# SCH_efoil_tracker_v1_0_2026-07-30.net
KiCad netlist of a schematic drawn in EasyEDA
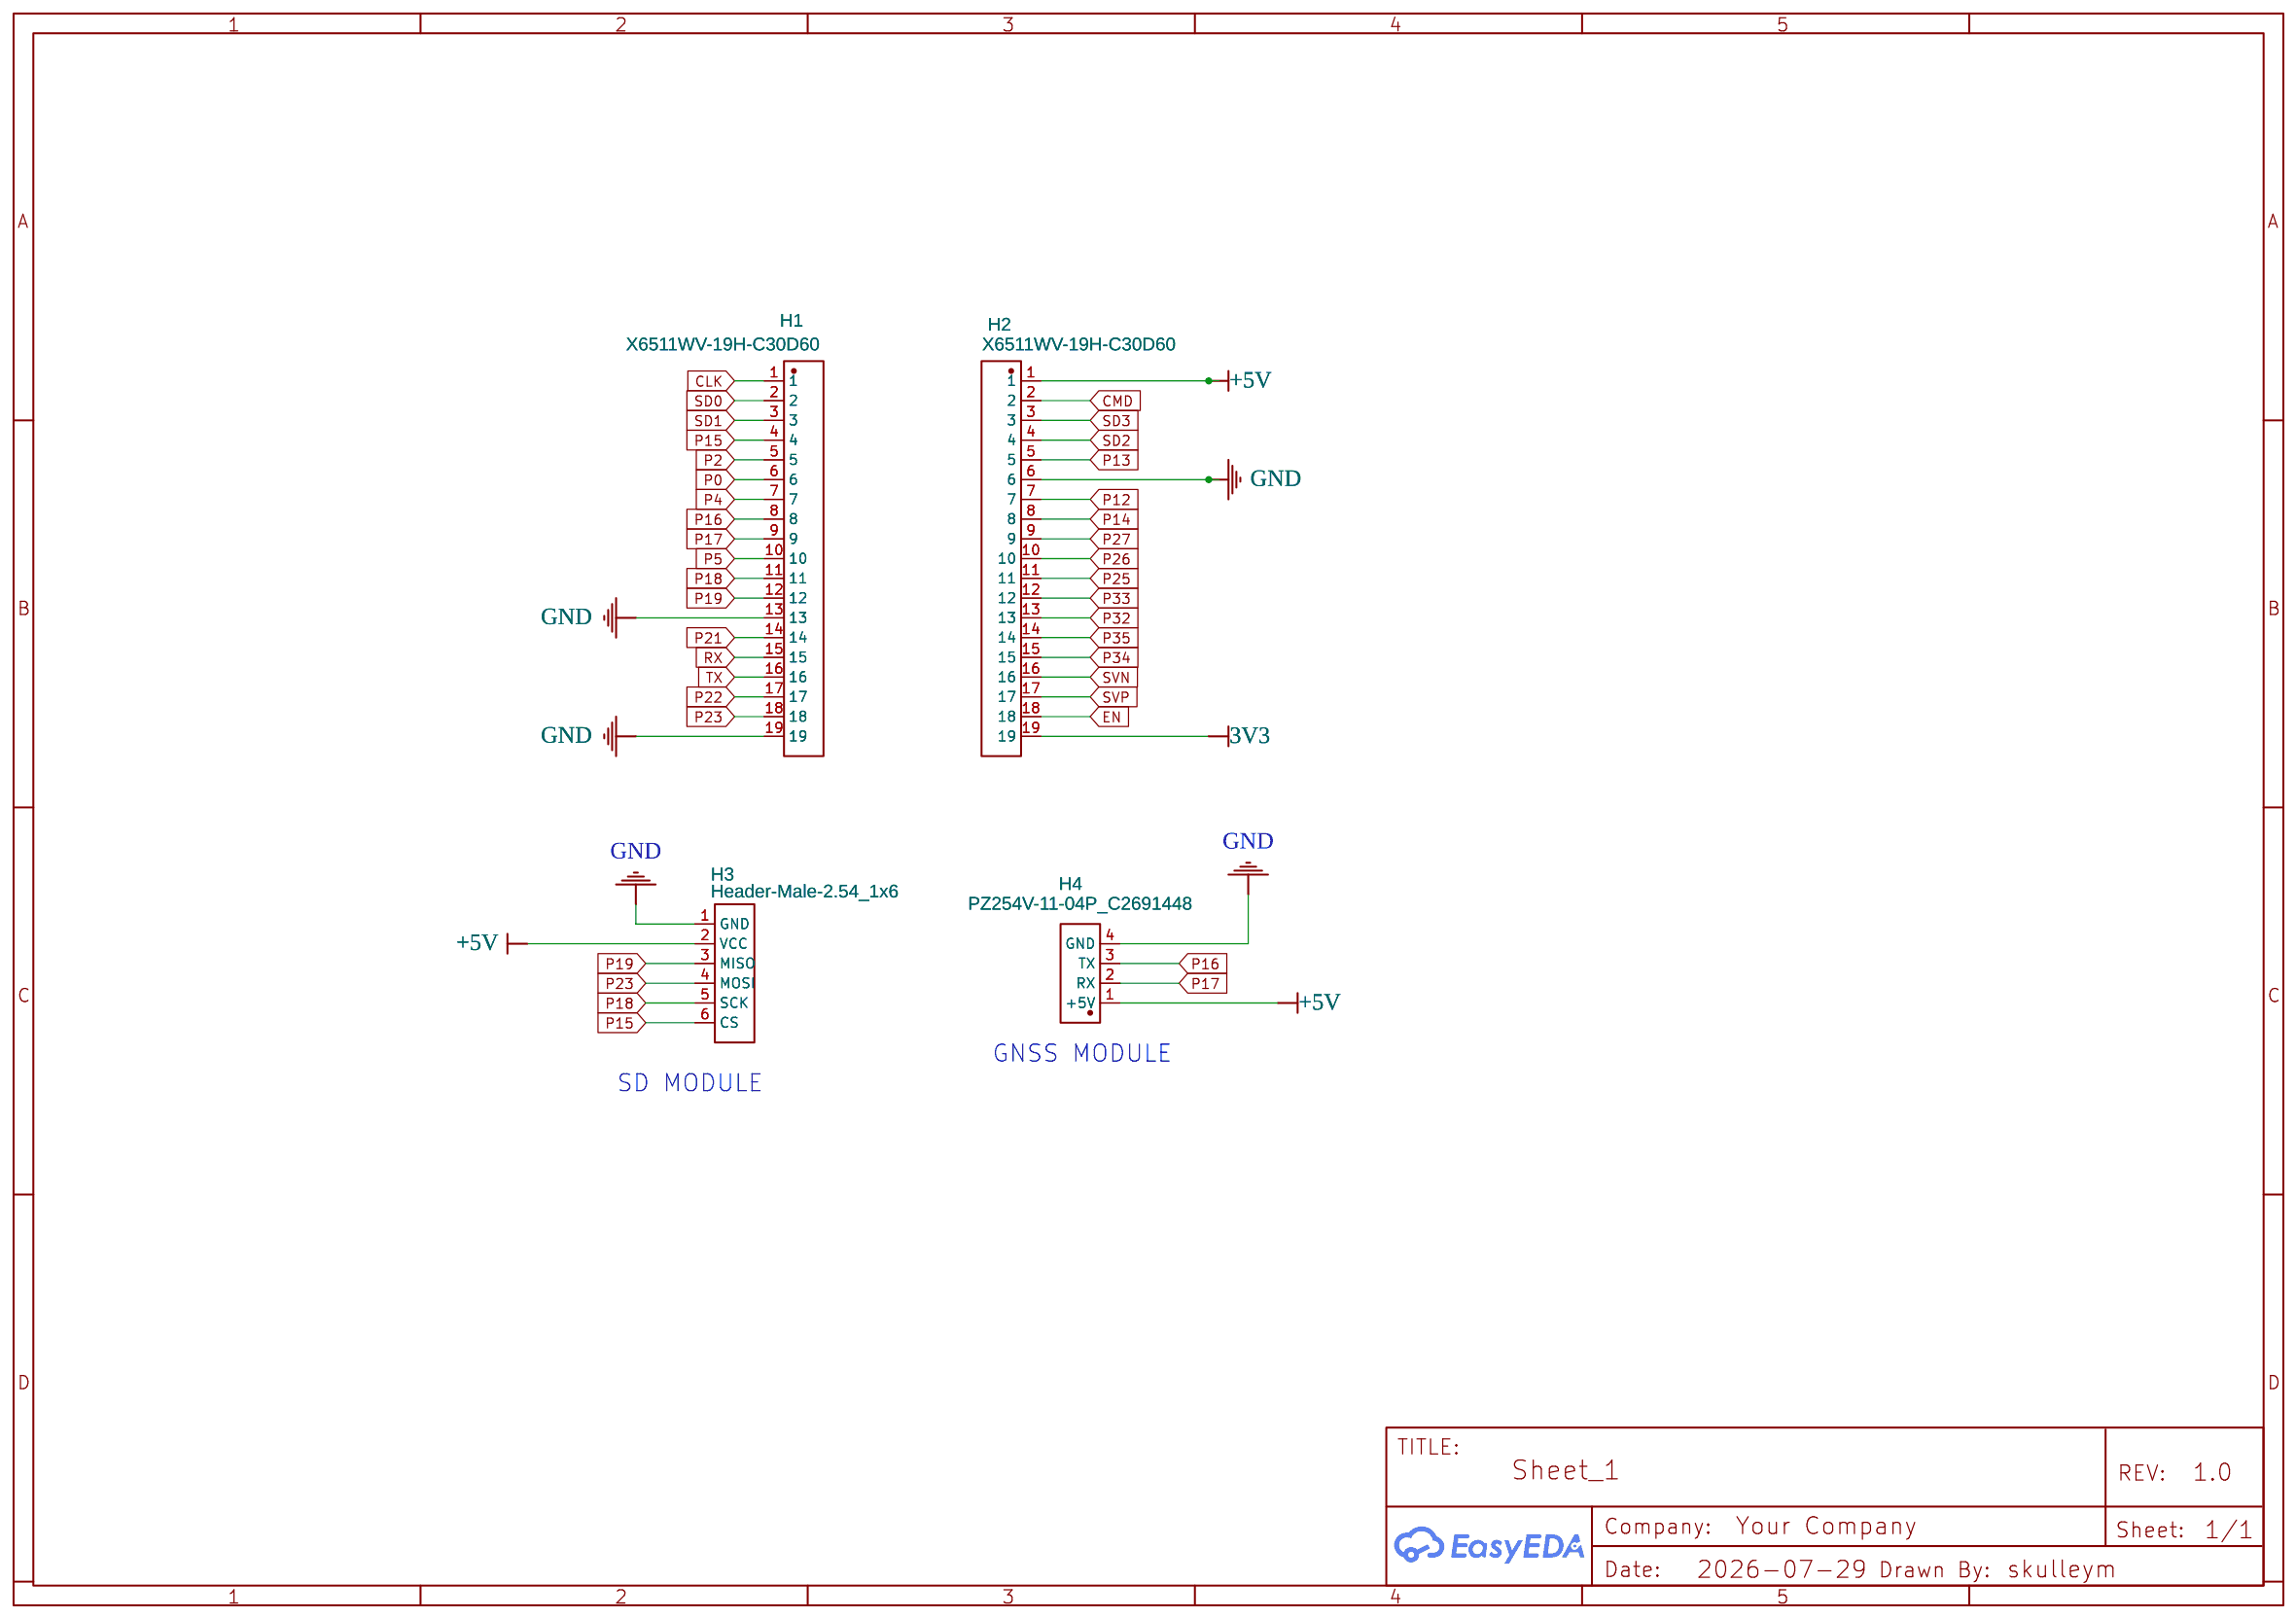
[diagram p0: schematic sheet]

(export (version "E")
  (design (tool "Eeschema 10.0.6"))
  (components
    (comp (ref "H1")
      (value "X6511WV-19H-C30D60")
      (fields
        (field (name "Manufacturer Part") "X6511WV-19H-C60D30")
        (field (name "Manufacturer") "XKB Connection(中国星坤)")
      )
      (libsource (lib "") (part "X6511WV-19H-C30D60_1"))
    )
    (comp (ref "H2")
      (value "X6511WV-19H-C30D60")
      (fields
        (field (name "Manufacturer Part") "X6511WV-19H-C60D30")
        (field (name "Manufacturer") "XKB Connection(中国星坤)")
      )
      (libsource (lib "") (part "X6511WV-19H-C30D60"))
    )
    (comp (ref "H3")
      (value "Header-Male-2.54_1x6")
      (fields (field (name "Manufacturer Part") "2.54-1x6P直针") (field (name "Manufacturer") "BOOMELE(博穆精密)"))
      (libsource (lib "") (part "Header-Male-2.54_1x6"))
    )
    (comp (ref "H4")
      (value "PZ254V-11-04P_C2691448")
      (fields (field (name "Manufacturer Part") "PZ254V-11-04P") (field (name "Manufacturer") "XFCN(兴飞)"))
      (libsource (lib "") (part "PZ254V-11-04P_C2691448"))
    )
  )
  (nets
    (net (code "1") (name "+5V") (class "Default")
      (node (ref "H2") (pin "1") (pinfunction "1_1") (pintype "unspecified"))
      (node (ref "H3") (pin "2") (pinfunction "VCC_2") (pintype "input"))
      (node (ref "H4") (pin "1") (pinfunction "+5V_1") (pintype "unspecified"))
    )
    (net (code "2") (name "3V3") (class "Default")
      (node (ref "H2") (pin "19") (pinfunction "19_19") (pintype "unspecified"))
    )
    (net (code "3") (name "CLK") (class "Default")
      (node (ref "H1") (pin "1") (pinfunction "1_1") (pintype "unspecified"))
    )
    (net (code "4") (name "CMD") (class "Default")
      (node (ref "H2") (pin "2") (pinfunction "2_2") (pintype "unspecified"))
    )
    (net (code "5") (name "EN") (class "Default")
      (node (ref "H2") (pin "18") (pinfunction "18_18") (pintype "unspecified"))
    )
    (net (code "6") (name "GND") (class "Default")
      (node (ref "H1") (pin "13") (pinfunction "13_13") (pintype "unspecified"))
      (node (ref "H1") (pin "19") (pinfunction "19_19") (pintype "unspecified"))
      (node (ref "H2") (pin "6") (pinfunction "6_6") (pintype "unspecified"))
      (node (ref "H3") (pin "1") (pinfunction "GND_1") (pintype "input"))
      (node (ref "H4") (pin "4") (pinfunction "GND_4") (pintype "unspecified"))
    )
    (net (code "7") (name "P0") (class "Default")
      (node (ref "H1") (pin "6") (pinfunction "6_6") (pintype "unspecified"))
    )
    (net (code "8") (name "P2") (class "Default")
      (node (ref "H1") (pin "5") (pinfunction "5_5") (pintype "unspecified"))
    )
    (net (code "9") (name "P4") (class "Default")
      (node (ref "H1") (pin "7") (pinfunction "7_7") (pintype "unspecified"))
    )
    (net (code "10") (name "P5") (class "Default")
      (node (ref "H1") (pin "10") (pinfunction "10_10") (pintype "unspecified"))
    )
    (net (code "11") (name "P12") (class "Default")
      (node (ref "H2") (pin "7") (pinfunction "7_7") (pintype "unspecified"))
    )
    (net (code "12") (name "P13") (class "Default")
      (node (ref "H2") (pin "5") (pinfunction "5_5") (pintype "unspecified"))
    )
    (net (code "13") (name "P14") (class "Default")
      (node (ref "H2") (pin "8") (pinfunction "8_8") (pintype "unspecified"))
    )
    (net (code "14") (name "P15") (class "Default")
      (node (ref "H1") (pin "4") (pinfunction "4_4") (pintype "unspecified"))
      (node (ref "H3") (pin "6") (pinfunction "CS_6") (pintype "input"))
    )
    (net (code "15") (name "P16") (class "Default")
      (node (ref "H1") (pin "8") (pinfunction "8_8") (pintype "unspecified"))
      (node (ref "H4") (pin "3") (pinfunction "TX_3") (pintype "unspecified"))
    )
    (net (code "16") (name "P17") (class "Default")
      (node (ref "H1") (pin "9") (pinfunction "9_9") (pintype "unspecified"))
      (node (ref "H4") (pin "2") (pinfunction "RX_2") (pintype "unspecified"))
    )
    (net (code "17") (name "P18") (class "Default")
      (node (ref "H1") (pin "11") (pinfunction "11_11") (pintype "unspecified"))
      (node (ref "H3") (pin "5") (pinfunction "SCK_5") (pintype "input"))
    )
    (net (code "18") (name "P19") (class "Default")
      (node (ref "H1") (pin "12") (pinfunction "12_12") (pintype "unspecified"))
      (node (ref "H3") (pin "3") (pinfunction "MISO_3") (pintype "input"))
    )
    (net (code "19") (name "P21") (class "Default")
      (node (ref "H1") (pin "14") (pinfunction "14_14") (pintype "unspecified"))
    )
    (net (code "20") (name "P22") (class "Default")
      (node (ref "H1") (pin "17") (pinfunction "17_17") (pintype "unspecified"))
    )
    (net (code "21") (name "P23") (class "Default")
      (node (ref "H1") (pin "18") (pinfunction "18_18") (pintype "unspecified"))
      (node (ref "H3") (pin "4") (pinfunction "MOSI_4") (pintype "input"))
    )
    (net (code "22") (name "P25") (class "Default")
      (node (ref "H2") (pin "11") (pinfunction "11_11") (pintype "unspecified"))
    )
    (net (code "23") (name "P26") (class "Default")
      (node (ref "H2") (pin "10") (pinfunction "10_10") (pintype "unspecified"))
    )
    (net (code "24") (name "P27") (class "Default")
      (node (ref "H2") (pin "9") (pinfunction "9_9") (pintype "unspecified"))
    )
    (net (code "25") (name "P32") (class "Default")
      (node (ref "H2") (pin "13") (pinfunction "13_13") (pintype "unspecified"))
    )
    (net (code "26") (name "P33") (class "Default")
      (node (ref "H2") (pin "12") (pinfunction "12_12") (pintype "unspecified"))
    )
    (net (code "27") (name "P34") (class "Default")
      (node (ref "H2") (pin "15") (pinfunction "15_15") (pintype "unspecified"))
    )
    (net (code "28") (name "P35") (class "Default")
      (node (ref "H2") (pin "14") (pinfunction "14_14") (pintype "unspecified"))
    )
    (net (code "29") (name "RX") (class "Default")
      (node (ref "H1") (pin "15") (pinfunction "15_15") (pintype "unspecified"))
    )
    (net (code "30") (name "SD0") (class "Default")
      (node (ref "H1") (pin "2") (pinfunction "2_2") (pintype "unspecified"))
    )
    (net (code "31") (name "SD1") (class "Default")
      (node (ref "H1") (pin "3") (pinfunction "3_3") (pintype "unspecified"))
    )
    (net (code "32") (name "SD2") (class "Default")
      (node (ref "H2") (pin "4") (pinfunction "4_4") (pintype "unspecified"))
    )
    (net (code "33") (name "SD3") (class "Default")
      (node (ref "H2") (pin "3") (pinfunction "3_3") (pintype "unspecified"))
    )
    (net (code "34") (name "SVN") (class "Default")
      (node (ref "H2") (pin "16") (pinfunction "16_16") (pintype "unspecified"))
    )
    (net (code "35") (name "SVP") (class "Default")
      (node (ref "H2") (pin "17") (pinfunction "17_17") (pintype "unspecified"))
    )
    (net (code "36") (name "TX") (class "Default")
      (node (ref "H1") (pin "16") (pinfunction "16_16") (pintype "unspecified"))
    )
  )
)
